# iSystem-FDCAN.net
KiCad netlist of a schematic drawn in Altium Designer
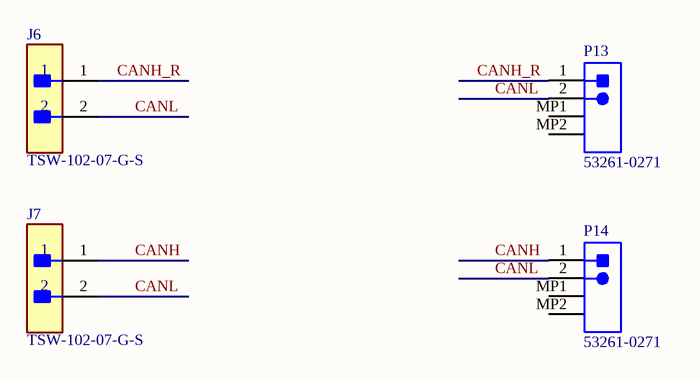
[diagram p0: iSystem-FDCAN.SchDoc]

(export (version "E")
  (design (tool "Eeschema 10.0.6"))
  (components
    (comp (ref "J6")
      (value "TSW-102-07-G-S")
      (footprint "FP-TSW-102-07-G-S-MFG")
      (description "CONN HEADER VERT 2POS 2.54MM")
      (fields
        (field (name "MANUFACTURER") "Samtec")
        (field (name "OCTOPART") "https://octopart.com/tsw-102-07-g-s-samtec-272197")
      )
      (libsource (lib "Altium Content Vault") (part "3bc925449376181038e59eaffc5286c"))
    )
    (comp (ref "J7")
      (value "TSW-102-07-G-S")
      (footprint "FP-TSW-102-07-G-S-MFG")
      (description "CONN HEADER VERT 2POS 2.54MM")
      (fields
        (field (name "MANUFACTURER") "Samtec")
        (field (name "OCTOPART") "https://octopart.com/tsw-102-07-g-s-samtec-272197")
      )
      (libsource (lib "Altium Content Vault") (part "3bc925449376181038e59eaffc5286c"))
    )
    (comp (ref "P13")
      (value "53261-0271")
      (footprint "MOLX-53261-0271_V")
      (description "PicoBlade(TM) Header, Right Angle, -40 to 85 degC, 2-Pin SMD, RoHS, Tape and Reel")
      (fields (field (name "MANUFACTURER") "Molex"))
      (libsource (lib "Altium Content Vault") (part "CN-1P-2M-R2"))
    )
    (comp (ref "P14")
      (value "53261-0271")
      (footprint "MOLX-53261-0271_V")
      (description "PicoBlade(TM) Header, Right Angle, -40 to 85 degC, 2-Pin SMD, RoHS, Tape and Reel")
      (fields (field (name "MANUFACTURER") "Molex"))
      (libsource (lib "Altium Content Vault") (part "CN-1P-2M-R2"))
    )
  )
  (nets
    (net (code "1") (name "/CANH") (class "Default")
      (node (ref "J7") (pin "1") (pinfunction "1_1") (pintype "passive"))
      (node (ref "P14") (pin "1") (pinfunction "1_1") (pintype "passive"))
    )
    (net (code "2") (name "/CANH_R") (class "Default")
      (node (ref "J6") (pin "1") (pinfunction "1_1") (pintype "passive"))
      (node (ref "P13") (pin "1") (pinfunction "1_1") (pintype "passive"))
    )
    (net (code "3") (name "/CANL") (class "Default")
      (node (ref "J6") (pin "2") (pinfunction "2_2") (pintype "passive"))
      (node (ref "J7") (pin "2") (pinfunction "2_2") (pintype "passive"))
      (node (ref "P13") (pin "2") (pinfunction "2_2") (pintype "passive"))
      (node (ref "P14") (pin "2") (pinfunction "2_2") (pintype "passive"))
    )
    (net (code "4") (name "unconnected-(P13-PadMP1)") (class "Default")
      (node (ref "P13") (pin "MP1") (pinfunction "MP1_MP1") (pintype "passive"))
    )
    (net (code "5") (name "unconnected-(P13-PadMP2)") (class "Default")
      (node (ref "P13") (pin "MP2") (pinfunction "MP2_MP2") (pintype "passive"))
    )
    (net (code "6") (name "unconnected-(P14-PadMP1)") (class "Default")
      (node (ref "P14") (pin "MP1") (pinfunction "MP1_MP1") (pintype "passive"))
    )
    (net (code "7") (name "unconnected-(P14-PadMP2)") (class "Default")
      (node (ref "P14") (pin "MP2") (pinfunction "MP2_MP2") (pintype "passive"))
    )
  )
)
